# IMU.net
KiCad netlist of a schematic drawn in Altium Designer
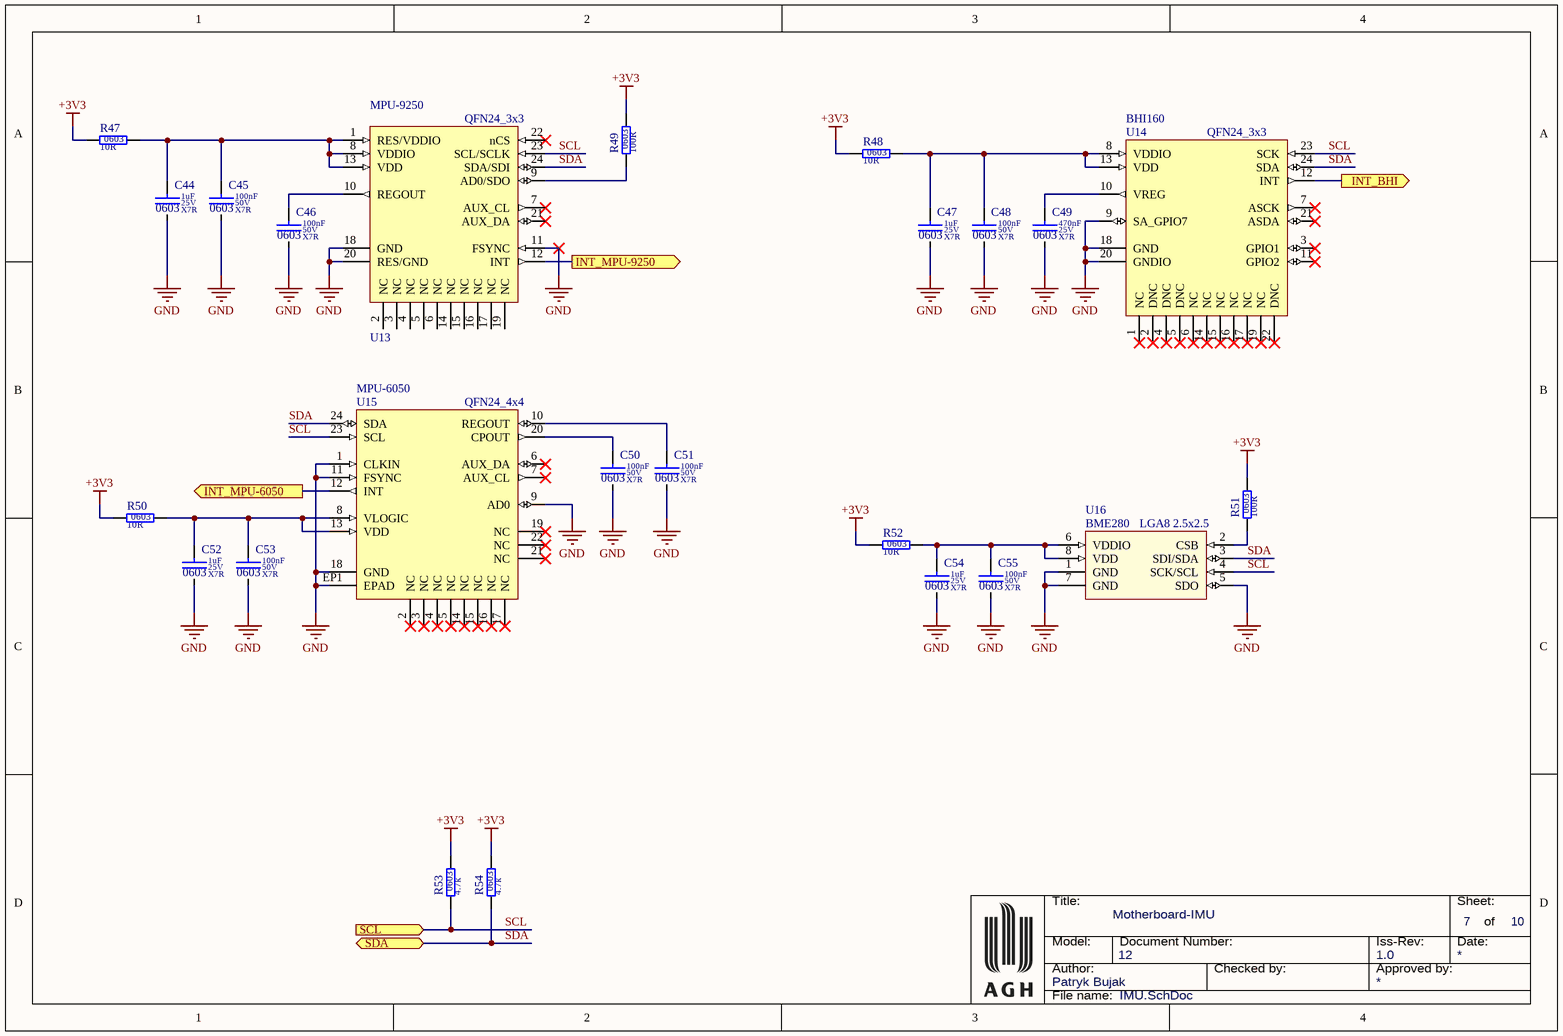
[diagram p0: IMU.SchDoc]

(export (version "E")
  (design (tool "Eeschema 10.0.6"))
  (components
    (comp (ref "C44")
      (value "1uF")
      (footprint "C_0603_1608")
      (description "Capacitor")
      (fields
        (field (name "DIELECTRIC") "X7R")
        (field (name "VOLTAGE") "25V")
        (field (name "SCH_FOOTPRINT") "0603")
        (field (name "PART NUMBER") "C_1uF_25V_X7R_0603_10")
        (field (name "MANUFACTURER") "Samsung")
      )
      (libsource (lib "Library") (part "C"))
    )
    (comp (ref "C45")
      (value "100nF")
      (footprint "C_0603_1608")
      (description "Capacitor")
      (fields
        (field (name "DIELECTRIC") "X7R")
        (field (name "VOLTAGE") "50V")
        (field (name "SCH_FOOTPRINT") "0603")
        (field (name "PART NUMBER") "C_100nF_50V_X7R_0603_5")
        (field (name "MANUFACTURER") "Samsung")
      )
      (libsource (lib "Library") (part "C"))
    )
    (comp (ref "C46")
      (value "100nF")
      (footprint "C_0603_1608")
      (description "Capacitor")
      (fields
        (field (name "DIELECTRIC") "X7R")
        (field (name "VOLTAGE") "50V")
        (field (name "SCH_FOOTPRINT") "0603")
        (field (name "PART NUMBER") "C_100nF_50V_X7R_0603_5")
        (field (name "MANUFACTURER") "Samsung")
      )
      (libsource (lib "Library") (part "C"))
    )
    (comp (ref "C47")
      (value "1uF")
      (footprint "C_0603_1608")
      (description "Capacitor")
      (fields
        (field (name "DIELECTRIC") "X7R")
        (field (name "VOLTAGE") "25V")
        (field (name "SCH_FOOTPRINT") "0603")
        (field (name "PART NUMBER") "C_1uF_25V_X7R_0603_10")
        (field (name "MANUFACTURER") "Samsung")
      )
      (libsource (lib "Library") (part "C"))
    )
    (comp (ref "C48")
      (value "100nF")
      (footprint "C_0603_1608")
      (description "Capacitor")
      (fields
        (field (name "DIELECTRIC") "X7R")
        (field (name "VOLTAGE") "50V")
        (field (name "SCH_FOOTPRINT") "0603")
        (field (name "PART NUMBER") "C_100nF_50V_X7R_0603_5")
        (field (name "MANUFACTURER") "Samsung")
      )
      (libsource (lib "Library") (part "C"))
    )
    (comp (ref "C49")
      (value "470nF")
      (footprint "C_0603_1608")
      (description "Capacitor")
      (fields
        (field (name "DIELECTRIC") "X7R")
        (field (name "VOLTAGE") "25V")
        (field (name "SCH_FOOTPRINT") "0603")
        (field (name "PART NUMBER") "C_470nF_25V_X7R_0603_10")
        (field (name "MANUFACTURER") "Murata")
      )
      (libsource (lib "Library") (part "C"))
    )
    (comp (ref "C50")
      (value "100nF")
      (footprint "C_0603_1608")
      (description "Capacitor")
      (fields
        (field (name "DIELECTRIC") "X7R")
        (field (name "VOLTAGE") "50V")
        (field (name "SCH_FOOTPRINT") "0603")
        (field (name "PART NUMBER") "C_100nF_50V_X7R_0603_5")
        (field (name "MANUFACTURER") "Samsung")
      )
      (libsource (lib "Library") (part "C"))
    )
    (comp (ref "C51")
      (value "100nF")
      (footprint "C_0603_1608")
      (description "Capacitor")
      (fields
        (field (name "DIELECTRIC") "X7R")
        (field (name "VOLTAGE") "50V")
        (field (name "SCH_FOOTPRINT") "0603")
        (field (name "PART NUMBER") "C_100nF_50V_X7R_0603_5")
        (field (name "MANUFACTURER") "Samsung")
      )
      (libsource (lib "Library") (part "C"))
    )
    (comp (ref "C52")
      (value "1uF")
      (footprint "C_0603_1608")
      (description "Capacitor")
      (fields
        (field (name "DIELECTRIC") "X7R")
        (field (name "VOLTAGE") "25V")
        (field (name "SCH_FOOTPRINT") "0603")
        (field (name "PART NUMBER") "C_1uF_25V_X7R_0603_10")
        (field (name "MANUFACTURER") "Samsung")
      )
      (libsource (lib "Library") (part "C"))
    )
    (comp (ref "C53")
      (value "100nF")
      (footprint "C_0603_1608")
      (description "Capacitor")
      (fields
        (field (name "DIELECTRIC") "X7R")
        (field (name "VOLTAGE") "50V")
        (field (name "SCH_FOOTPRINT") "0603")
        (field (name "PART NUMBER") "C_100nF_50V_X7R_0603_5")
        (field (name "MANUFACTURER") "Samsung")
      )
      (libsource (lib "Library") (part "C"))
    )
    (comp (ref "C54")
      (value "1uF")
      (footprint "C_0603_1608")
      (description "Capacitor")
      (fields
        (field (name "DIELECTRIC") "X7R")
        (field (name "VOLTAGE") "25V")
        (field (name "SCH_FOOTPRINT") "0603")
        (field (name "PART NUMBER") "C_1uF_25V_X7R_0603_10")
        (field (name "MANUFACTURER") "Samsung")
      )
      (libsource (lib "Library") (part "C"))
    )
    (comp (ref "C55")
      (value "100nF")
      (footprint "C_0603_1608")
      (description "Capacitor")
      (fields
        (field (name "DIELECTRIC") "X7R")
        (field (name "VOLTAGE") "50V")
        (field (name "SCH_FOOTPRINT") "0603")
        (field (name "PART NUMBER") "C_100nF_50V_X7R_0603_5")
        (field (name "MANUFACTURER") "Samsung")
      )
      (libsource (lib "Library") (part "C"))
    )
    (comp (ref "R47")
      (value "10R")
      (footprint "R_0603_1608")
      (fields
        (field (name "SCH_FOOTPRINT") "0603")
        (field (name "PART NUMBER") "R_10R_0603_1")
        (field (name "VOLTAGE") "50V")
        (field (name "POWER") "100mW")
      )
      (libsource (lib "Library") (part "R"))
    )
    (comp (ref "R48")
      (value "10R")
      (footprint "R_0603_1608")
      (fields
        (field (name "SCH_FOOTPRINT") "0603")
        (field (name "PART NUMBER") "R_10R_0603_1")
        (field (name "VOLTAGE") "50V")
        (field (name "POWER") "100mW")
      )
      (libsource (lib "Library") (part "R"))
    )
    (comp (ref "R49")
      (value "100R")
      (footprint "R_0603_1608")
      (fields
        (field (name "SCH_FOOTPRINT") "0603")
        (field (name "PART NUMBER") "R_100R_0603_1")
        (field (name "VOLTAGE") "50V")
        (field (name "POWER") "100mW")
      )
      (libsource (lib "Library") (part "R"))
    )
    (comp (ref "R50")
      (value "10R")
      (footprint "R_0603_1608")
      (fields
        (field (name "SCH_FOOTPRINT") "0603")
        (field (name "PART NUMBER") "R_10R_0603_1")
        (field (name "VOLTAGE") "50V")
        (field (name "POWER") "100mW")
      )
      (libsource (lib "Library") (part "R"))
    )
    (comp (ref "R51")
      (value "100R")
      (footprint "R_0603_1608")
      (fields
        (field (name "SCH_FOOTPRINT") "0603")
        (field (name "PART NUMBER") "R_100R_0603_1")
        (field (name "VOLTAGE") "50V")
        (field (name "POWER") "100mW")
      )
      (libsource (lib "Library") (part "R"))
    )
    (comp (ref "R52")
      (value "10R")
      (footprint "R_0603_1608")
      (fields
        (field (name "SCH_FOOTPRINT") "0603")
        (field (name "PART NUMBER") "R_10R_0603_1")
        (field (name "VOLTAGE") "50V")
        (field (name "POWER") "100mW")
      )
      (libsource (lib "Library") (part "R"))
    )
    (comp (ref "R53")
      (value "4.7k")
      (footprint "R_0603_1608")
      (fields
        (field (name "SCH_FOOTPRINT") "0603")
        (field (name "PART NUMBER") "R_4.7k_0603_1")
        (field (name "VOLTAGE") "75V")
        (field (name "POWER") "100mW")
      )
      (libsource (lib "Library") (part "R"))
    )
    (comp (ref "R54")
      (value "4.7k")
      (footprint "R_0603_1608")
      (fields
        (field (name "SCH_FOOTPRINT") "0603")
        (field (name "PART NUMBER") "R_4.7k_0603_1")
        (field (name "VOLTAGE") "75V")
        (field (name "POWER") "100mW")
      )
      (libsource (lib "Library") (part "R"))
    )
    (comp (ref "U13")
      (value "MPU-9250")
      (footprint "QFN24_3x3")
      (fields
        (field (name "SCH_FOOTPRINT") "QFN24_3x3")
        (field (name "PART NUMBER") "U_MPU-9250")
        (field (name "MANUFACTURER") "InvenSense")
        (field (name "Comment") "Nine-Axis (Gyro + Accelerometer + Compass) MEMS MotionTracking Device")
      )
      (libsource (lib "Library") (part "U_MPU-9250"))
    )
    (comp (ref "U14")
      (value "BHI160")
      (footprint "QFN24_3x3")
      (fields
        (field (name "SCH_FOOTPRINT") "QFN24_3x3")
        (field (name "PART NUMBER") "U_BHI160")
        (field (name "MANUFACTURER") "Bosch Tools")
        (field (name "Comment") "Three Axis Ultra Low Power Sensor Hub - LGA-24")
      )
      (libsource (lib "Library") (part "U_BHI160"))
    )
    (comp (ref "U15")
      (value "MPU-6050")
      (footprint "QFN24_4x4")
      (fields
        (field (name "SCH_FOOTPRINT") "QFN24_4x4")
        (field (name "PART NUMBER") "U_MPU-6050")
        (field (name "MANUFACTURER") "InvenSense")
        (field (name "Comment") "Accelerometer and Gyroscope Digital Output 2.5V/3.3V 24-Pin QFN EP")
      )
      (libsource (lib "Library") (part "U_MPU-6050"))
    )
    (comp (ref "U16")
      (value "BME280")
      (footprint "LGA8_2.5x2.5")
      (fields
        (field (name "SCH_FOOTPRINT") "LGA8 2.5x2.5")
        (field (name "PART NUMBER") "U_BME280")
        (field (name "MANUFACTURER") "Bosch Tools")
        (field (name "Comment") "Combined humidity and pressure sensor")
      )
      (libsource (lib "Library") (part "U_BME280"))
    )
  )
  (nets
    (net (code "1") (name "+3V3") (class "Default")
      (node (ref "R47") (pin "1") (pinfunction "1_1") (pintype "passive"))
      (node (ref "R48") (pin "1") (pinfunction "1_1") (pintype "passive"))
      (node (ref "R49") (pin "2") (pinfunction "2_2") (pintype "passive"))
      (node (ref "R50") (pin "1") (pinfunction "1_1") (pintype "passive"))
      (node (ref "R51") (pin "2") (pinfunction "2_2") (pintype "passive"))
      (node (ref "R52") (pin "1") (pinfunction "1_1") (pintype "passive"))
      (node (ref "R53") (pin "2") (pinfunction "2_2") (pintype "passive"))
      (node (ref "R54") (pin "2") (pinfunction "2_2") (pintype "passive"))
    )
    (net (code "2") (name "/INT_BHI") (class "Default")
      (node (ref "U14") (pin "12") (pinfunction "INT_12") (pintype "output"))
    )
    (net (code "3") (name "/INT_MPU-6050") (class "Default")
      (node (ref "U15") (pin "12") (pinfunction "INT_12") (pintype "output"))
    )
    (net (code "4") (name "/INT_MPU-9250") (class "Default")
      (node (ref "U13") (pin "12") (pinfunction "INT_12") (pintype "output"))
    )
    (net (code "5") (name "/SCL") (class "Default")
      (node (ref "R53") (pin "1") (pinfunction "1_1") (pintype "passive"))
      (node (ref "U13") (pin "23") (pinfunction "SCL/SCLK_23") (pintype "input"))
      (node (ref "U14") (pin "23") (pinfunction "SCK_23") (pintype "input"))
      (node (ref "U15") (pin "23") (pinfunction "SCL_23") (pintype "input"))
      (node (ref "U16") (pin "4") (pinfunction "SCK/SCL_4") (pintype "input"))
    )
    (net (code "6") (name "/SDA") (class "Default")
      (node (ref "R54") (pin "1") (pinfunction "1_1") (pintype "passive"))
      (node (ref "U13") (pin "24") (pinfunction "SDA/SDI_24") (pintype "bidirectional"))
      (node (ref "U14") (pin "24") (pinfunction "SDA_24") (pintype "bidirectional"))
      (node (ref "U15") (pin "24") (pinfunction "SDA_24") (pintype "bidirectional"))
      (node (ref "U16") (pin "3") (pinfunction "SDI/SDA_3") (pintype "bidirectional"))
    )
    (net (code "7") (name "GND") (class "Default")
      (node (ref "C44") (pin "2") (pinfunction "2_2") (pintype "passive"))
      (node (ref "C45") (pin "2") (pinfunction "2_2") (pintype "passive"))
      (node (ref "C46") (pin "2") (pinfunction "2_2") (pintype "passive"))
      (node (ref "C47") (pin "2") (pinfunction "2_2") (pintype "passive"))
      (node (ref "C48") (pin "2") (pinfunction "2_2") (pintype "passive"))
      (node (ref "C49") (pin "2") (pinfunction "2_2") (pintype "passive"))
      (node (ref "C50") (pin "2") (pinfunction "2_2") (pintype "passive"))
      (node (ref "C51") (pin "2") (pinfunction "2_2") (pintype "passive"))
      (node (ref "C52") (pin "2") (pinfunction "2_2") (pintype "passive"))
      (node (ref "C53") (pin "2") (pinfunction "2_2") (pintype "passive"))
      (node (ref "C54") (pin "2") (pinfunction "2_2") (pintype "passive"))
      (node (ref "C55") (pin "2") (pinfunction "2_2") (pintype "passive"))
      (node (ref "U13") (pin "11") (pinfunction "FSYNC_11") (pintype "input"))
      (node (ref "U13") (pin "18") (pinfunction "GND_18") (pintype "power_in"))
      (node (ref "U13") (pin "20") (pinfunction "RES/GND_20") (pintype "power_in"))
      (node (ref "U14") (pin "18") (pinfunction "GND_18") (pintype "power_in"))
      (node (ref "U14") (pin "20") (pinfunction "GNDIO_20") (pintype "power_in"))
      (node (ref "U14") (pin "9") (pinfunction "SA_GPIO7_9") (pintype "bidirectional"))
      (node (ref "U15") (pin "1") (pinfunction "CLKIN_1") (pintype "input"))
      (node (ref "U15") (pin "11") (pinfunction "FSYNC_11") (pintype "input"))
      (node (ref "U15") (pin "18") (pinfunction "GND_18") (pintype "power_in"))
      (node (ref "U15") (pin "9") (pinfunction "AD0_9") (pintype "bidirectional"))
      (node (ref "U15") (pin "EP1") (pinfunction "EPAD_EP1") (pintype "passive"))
      (node (ref "U16") (pin "1") (pinfunction "GND_1") (pintype "power_in"))
      (node (ref "U16") (pin "5") (pinfunction "SDO_5") (pintype "bidirectional"))
      (node (ref "U16") (pin "7") (pinfunction "GND_7") (pintype "power_in"))
    )
    (net (code "8") (name "Net-(U13-AD0{slash}SDO)") (class "Default")
      (node (ref "R49") (pin "1") (pinfunction "1_1") (pintype "passive"))
      (node (ref "U13") (pin "9") (pinfunction "AD0/SDO_9") (pintype "bidirectional"))
    )
    (net (code "9") (name "Net-(U13-REGOUT)") (class "Default")
      (node (ref "C46") (pin "1") (pinfunction "1_1") (pintype "passive"))
      (node (ref "U13") (pin "10") (pinfunction "REGOUT_10") (pintype "output"))
    )
    (net (code "10") (name "Net-(U13-RES{slash}VDDIO)") (class "Default")
      (node (ref "C44") (pin "1") (pinfunction "1_1") (pintype "passive"))
      (node (ref "C45") (pin "1") (pinfunction "1_1") (pintype "passive"))
      (node (ref "R47") (pin "2") (pinfunction "2_2") (pintype "passive"))
      (node (ref "U13") (pin "1") (pinfunction "RES/VDDIO_1") (pintype "input"))
      (node (ref "U13") (pin "13") (pinfunction "VDD_13") (pintype "input"))
      (node (ref "U13") (pin "8") (pinfunction "VDDIO_8") (pintype "input"))
    )
    (net (code "11") (name "Net-(U14-VDD)") (class "Default")
      (node (ref "C47") (pin "1") (pinfunction "1_1") (pintype "passive"))
      (node (ref "C48") (pin "1") (pinfunction "1_1") (pintype "passive"))
      (node (ref "R48") (pin "2") (pinfunction "2_2") (pintype "passive"))
      (node (ref "U14") (pin "13") (pinfunction "VDD_13") (pintype "input"))
      (node (ref "U14") (pin "8") (pinfunction "VDDIO_8") (pintype "input"))
    )
    (net (code "12") (name "Net-(U14-VREG)") (class "Default")
      (node (ref "C49") (pin "1") (pinfunction "1_1") (pintype "passive"))
      (node (ref "U14") (pin "10") (pinfunction "VREG_10") (pintype "output"))
    )
    (net (code "13") (name "Net-(U15-CPOUT)") (class "Default")
      (node (ref "C50") (pin "1") (pinfunction "1_1") (pintype "passive"))
      (node (ref "U15") (pin "20") (pinfunction "CPOUT_20") (pintype "output"))
    )
    (net (code "14") (name "Net-(U15-REGOUT)") (class "Default")
      (node (ref "C51") (pin "1") (pinfunction "1_1") (pintype "passive"))
      (node (ref "U15") (pin "10") (pinfunction "REGOUT_10") (pintype "bidirectional"))
    )
    (net (code "15") (name "Net-(U15-VDD)") (class "Default")
      (node (ref "C52") (pin "1") (pinfunction "1_1") (pintype "passive"))
      (node (ref "C53") (pin "1") (pinfunction "1_1") (pintype "passive"))
      (node (ref "R50") (pin "2") (pinfunction "2_2") (pintype "passive"))
      (node (ref "U15") (pin "13") (pinfunction "VDD_13") (pintype "input"))
      (node (ref "U15") (pin "8") (pinfunction "VLOGIC_8") (pintype "input"))
    )
    (net (code "16") (name "Net-(U16-CSB)") (class "Default")
      (node (ref "R51") (pin "1") (pinfunction "1_1") (pintype "passive"))
      (node (ref "U16") (pin "2") (pinfunction "CSB_2") (pintype "input"))
    )
    (net (code "17") (name "Net-(U16-VDD)") (class "Default")
      (node (ref "C54") (pin "1") (pinfunction "1_1") (pintype "passive"))
      (node (ref "C55") (pin "1") (pinfunction "1_1") (pintype "passive"))
      (node (ref "R52") (pin "2") (pinfunction "2_2") (pintype "passive"))
      (node (ref "U16") (pin "6") (pinfunction "VDDIO_6") (pintype "input"))
      (node (ref "U16") (pin "8") (pinfunction "VDD_8") (pintype "input"))
    )
    (net (code "18") (name "unconnected-(U13-AUX_CL-Pad7)") (class "Default")
      (node (ref "U13") (pin "7") (pinfunction "AUX_CL_7") (pintype "output+no_connect"))
    )
    (net (code "19") (name "unconnected-(U13-AUX_DA-Pad21)") (class "Default")
      (node (ref "U13") (pin "21") (pinfunction "AUX_DA_21") (pintype "bidirectional+no_connect"))
    )
    (net (code "20") (name "unconnected-(U13-NC-Pad2)") (class "Default")
      (node (ref "U13") (pin "2") (pinfunction "NC_2") (pintype "passive"))
    )
    (net (code "21") (name "unconnected-(U13-NC-Pad3)") (class "Default")
      (node (ref "U13") (pin "3") (pinfunction "NC_3") (pintype "passive"))
    )
    (net (code "22") (name "unconnected-(U13-NC-Pad4)") (class "Default")
      (node (ref "U13") (pin "4") (pinfunction "NC_4") (pintype "passive"))
    )
    (net (code "23") (name "unconnected-(U13-NC-Pad5)") (class "Default")
      (node (ref "U13") (pin "5") (pinfunction "NC_5") (pintype "passive"))
    )
    (net (code "24") (name "unconnected-(U13-NC-Pad6)") (class "Default")
      (node (ref "U13") (pin "6") (pinfunction "NC_6") (pintype "passive"))
    )
    (net (code "25") (name "unconnected-(U13-NC-Pad14)") (class "Default")
      (node (ref "U13") (pin "14") (pinfunction "NC_14") (pintype "passive"))
    )
    (net (code "26") (name "unconnected-(U13-NC-Pad15)") (class "Default")
      (node (ref "U13") (pin "15") (pinfunction "NC_15") (pintype "passive"))
    )
    (net (code "27") (name "unconnected-(U13-NC-Pad16)") (class "Default")
      (node (ref "U13") (pin "16") (pinfunction "NC_16") (pintype "passive"))
    )
    (net (code "28") (name "unconnected-(U13-NC-Pad17)") (class "Default")
      (node (ref "U13") (pin "17") (pinfunction "NC_17") (pintype "passive"))
    )
    (net (code "29") (name "unconnected-(U13-NC-Pad19)") (class "Default")
      (node (ref "U13") (pin "19") (pinfunction "NC_19") (pintype "passive"))
    )
    (net (code "30") (name "unconnected-(U13-nCS-Pad22)") (class "Default")
      (node (ref "U13") (pin "22") (pinfunction "nCS_22") (pintype "input+no_connect"))
    )
    (net (code "31") (name "unconnected-(U14-ASCK-Pad7)") (class "Default")
      (node (ref "U14") (pin "7") (pinfunction "ASCK_7") (pintype "output+no_connect"))
    )
    (net (code "32") (name "unconnected-(U14-ASDA-Pad21)") (class "Default")
      (node (ref "U14") (pin "21") (pinfunction "ASDA_21") (pintype "bidirectional+no_connect"))
    )
    (net (code "33") (name "unconnected-(U14-DNC-Pad2)") (class "Default")
      (node (ref "U14") (pin "2") (pinfunction "DNC_2") (pintype "passive+no_connect"))
    )
    (net (code "34") (name "unconnected-(U14-DNC-Pad4)") (class "Default")
      (node (ref "U14") (pin "4") (pinfunction "DNC_4") (pintype "passive+no_connect"))
    )
    (net (code "35") (name "unconnected-(U14-DNC-Pad5)") (class "Default")
      (node (ref "U14") (pin "5") (pinfunction "DNC_5") (pintype "passive+no_connect"))
    )
    (net (code "36") (name "unconnected-(U14-DNC-Pad22)") (class "Default")
      (node (ref "U14") (pin "22") (pinfunction "DNC_22") (pintype "passive+no_connect"))
    )
    (net (code "37") (name "unconnected-(U14-GPIO1-Pad3)") (class "Default")
      (node (ref "U14") (pin "3") (pinfunction "GPIO1_3") (pintype "bidirectional+no_connect"))
    )
    (net (code "38") (name "unconnected-(U14-GPIO2-Pad11)") (class "Default")
      (node (ref "U14") (pin "11") (pinfunction "GPIO2_11") (pintype "bidirectional+no_connect"))
    )
    (net (code "39") (name "unconnected-(U14-NC-Pad1)") (class "Default")
      (node (ref "U14") (pin "1") (pinfunction "NC_1") (pintype "passive+no_connect"))
    )
    (net (code "40") (name "unconnected-(U14-NC-Pad6)") (class "Default")
      (node (ref "U14") (pin "6") (pinfunction "NC_6") (pintype "passive+no_connect"))
    )
    (net (code "41") (name "unconnected-(U14-NC-Pad14)") (class "Default")
      (node (ref "U14") (pin "14") (pinfunction "NC_14") (pintype "passive+no_connect"))
    )
    (net (code "42") (name "unconnected-(U14-NC-Pad15)") (class "Default")
      (node (ref "U14") (pin "15") (pinfunction "NC_15") (pintype "passive+no_connect"))
    )
    (net (code "43") (name "unconnected-(U14-NC-Pad16)") (class "Default")
      (node (ref "U14") (pin "16") (pinfunction "NC_16") (pintype "passive+no_connect"))
    )
    (net (code "44") (name "unconnected-(U14-NC-Pad17)") (class "Default")
      (node (ref "U14") (pin "17") (pinfunction "NC_17") (pintype "passive+no_connect"))
    )
    (net (code "45") (name "unconnected-(U14-NC-Pad19)") (class "Default")
      (node (ref "U14") (pin "19") (pinfunction "NC_19") (pintype "passive+no_connect"))
    )
    (net (code "46") (name "unconnected-(U15-AUX_CL-Pad7)") (class "Default")
      (node (ref "U15") (pin "7") (pinfunction "AUX_CL_7") (pintype "output+no_connect"))
    )
    (net (code "47") (name "unconnected-(U15-AUX_DA-Pad6)") (class "Default")
      (node (ref "U15") (pin "6") (pinfunction "AUX_DA_6") (pintype "bidirectional+no_connect"))
    )
    (net (code "48") (name "unconnected-(U15-NC-Pad2)") (class "Default")
      (node (ref "U15") (pin "2") (pinfunction "NC_2") (pintype "passive+no_connect"))
    )
    (net (code "49") (name "unconnected-(U15-NC-Pad3)") (class "Default")
      (node (ref "U15") (pin "3") (pinfunction "NC_3") (pintype "passive+no_connect"))
    )
    (net (code "50") (name "unconnected-(U15-NC-Pad4)") (class "Default")
      (node (ref "U15") (pin "4") (pinfunction "NC_4") (pintype "passive+no_connect"))
    )
    (net (code "51") (name "unconnected-(U15-NC-Pad5)") (class "Default")
      (node (ref "U15") (pin "5") (pinfunction "NC_5") (pintype "passive+no_connect"))
    )
    (net (code "52") (name "unconnected-(U15-NC-Pad14)") (class "Default")
      (node (ref "U15") (pin "14") (pinfunction "NC_14") (pintype "passive+no_connect"))
    )
    (net (code "53") (name "unconnected-(U15-NC-Pad15)") (class "Default")
      (node (ref "U15") (pin "15") (pinfunction "NC_15") (pintype "passive+no_connect"))
    )
    (net (code "54") (name "unconnected-(U15-NC-Pad16)") (class "Default")
      (node (ref "U15") (pin "16") (pinfunction "NC_16") (pintype "passive+no_connect"))
    )
    (net (code "55") (name "unconnected-(U15-NC-Pad17)") (class "Default")
      (node (ref "U15") (pin "17") (pinfunction "NC_17") (pintype "passive+no_connect"))
    )
    (net (code "56") (name "unconnected-(U15-NC-Pad19)") (class "Default")
      (node (ref "U15") (pin "19") (pinfunction "NC_19") (pintype "passive+no_connect"))
    )
    (net (code "57") (name "unconnected-(U15-NC-Pad21)") (class "Default")
      (node (ref "U15") (pin "21") (pinfunction "NC_21") (pintype "passive+no_connect"))
    )
    (net (code "58") (name "unconnected-(U15-NC-Pad22)") (class "Default")
      (node (ref "U15") (pin "22") (pinfunction "NC_22") (pintype "passive+no_connect"))
    )
  )
)
